# MUV_Sensors_pcb_all.net
KiCad netlist of a schematic drawn in EAGLE
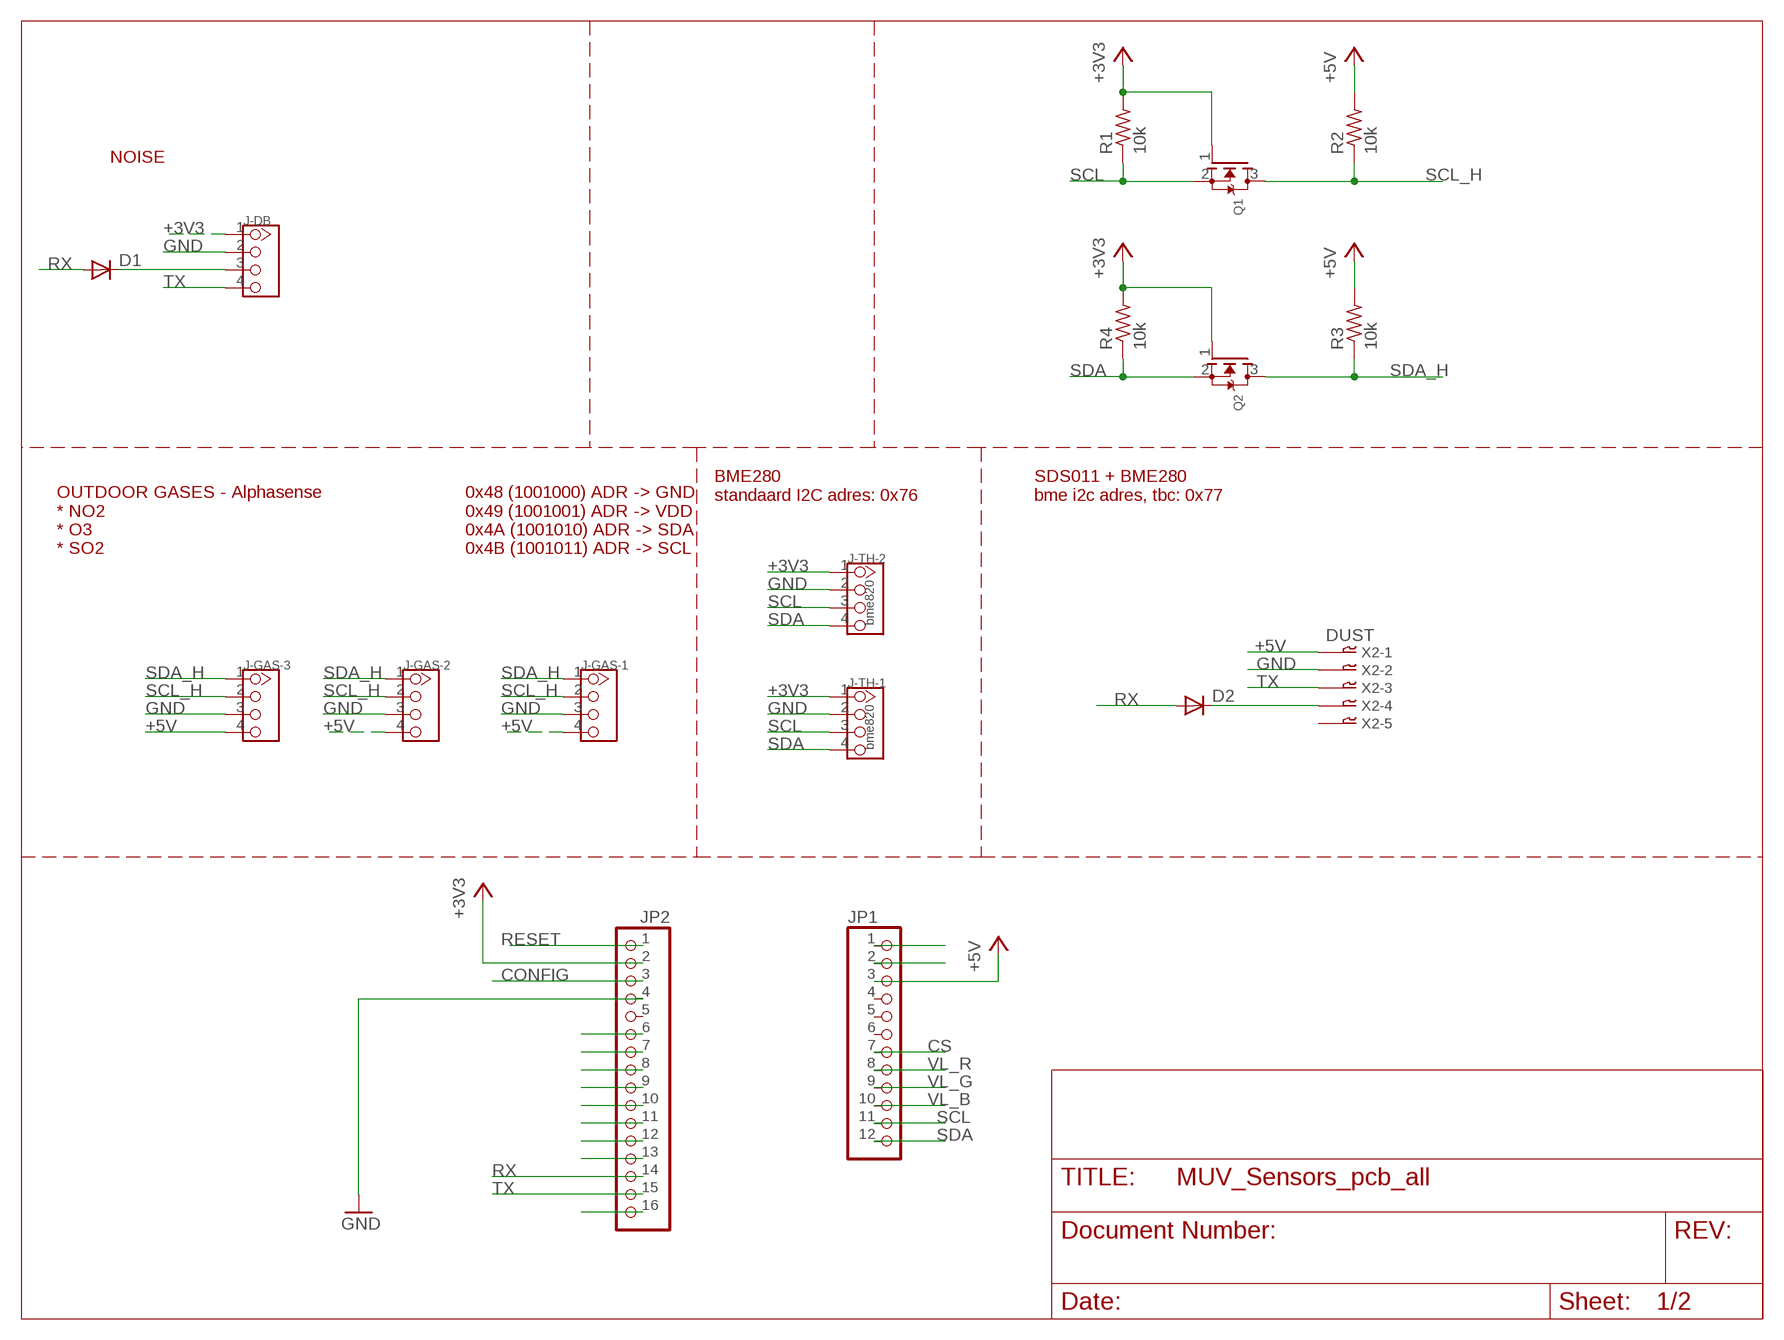
[diagram p0: schematic, sheet 1]

(export (version "E")
  (design (tool "Eeschema 10.0.6"))
  (components
    (comp (ref "D1")
      (value "DIODE-DO214AA")
      (footprint "eagle-import:DO214AA")
      (libsource (lib "eagle-import") (part "DIODE-DO214AA"))
    )
    (comp (ref "D2")
      (value "DIODE-DO214AA")
      (footprint "eagle-import:DO214AA")
      (libsource (lib "eagle-import") (part "DIODE-DO214AA"))
    )
    (comp (ref "J-DB")
      (value "TWIG-4P-2.0-2.0")
      (footprint "eagle-import:4P-2.0")
      (libsource (lib "eagle-import") (part "TWIG-4P-2.0-2.0"))
    )
    (comp (ref "J-GAS-1")
      (value "TWIG-4P-2.0-2.0")
      (footprint "eagle-import:4P-2.0")
      (libsource (lib "eagle-import") (part "TWIG-4P-2.0-2.0"))
    )
    (comp (ref "J-GAS-2")
      (value "TWIG-4P-2.0-2.0")
      (footprint "eagle-import:4P-2.0")
      (libsource (lib "eagle-import") (part "TWIG-4P-2.0-2.0"))
    )
    (comp (ref "J-GAS-3")
      (value "TWIG-4P-2.0-2.0")
      (footprint "eagle-import:4P-2.0")
      (libsource (lib "eagle-import") (part "TWIG-4P-2.0-2.0"))
    )
    (comp (ref "J-TH-1")
      (value "bme820")
      (footprint "eagle-import:4P-2.0")
      (libsource (lib "eagle-import") (part "TWIG-4P-2.0-2.0"))
    )
    (comp (ref "J-TH-2")
      (value "bme820")
      (footprint "eagle-import:4P-2.0")
      (libsource (lib "eagle-import") (part "TWIG-4P-2.0-2.0"))
    )
    (comp (ref "JP1")
      (value "HEADER-1X12OVAL")
      (footprint "eagle-import:1X12_OVAL")
      (libsource (lib "eagle-import") (part "HEADER-1X12OVAL"))
    )
    (comp (ref "JP2")
      (value "HEADER-1X16")
      (footprint "eagle-import:1X16_OVAL")
      (libsource (lib "eagle-import") (part "HEADER-1X16"))
    )
    (comp (ref "Q1")
      (value "MOSFET-NWIDE")
      (footprint "eagle-import:SOT23-WIDE")
      (libsource (lib "eagle-import") (part "MOSFET-NWIDE"))
    )
    (comp (ref "Q2")
      (value "MOSFET-NWIDE")
      (footprint "eagle-import:SOT23-WIDE")
      (libsource (lib "eagle-import") (part "MOSFET-NWIDE"))
    )
    (comp (ref "R1")
      (value "10k")
      (footprint "eagle-import:1206")
      (libsource (lib "eagle-import") (part "RESISTOR1206"))
    )
    (comp (ref "R2")
      (value "10k")
      (footprint "eagle-import:1206")
      (libsource (lib "eagle-import") (part "RESISTOR1206"))
    )
    (comp (ref "R3")
      (value "10k")
      (footprint "eagle-import:1206")
      (libsource (lib "eagle-import") (part "RESISTOR1206"))
    )
    (comp (ref "R4")
      (value "10k")
      (footprint "eagle-import:1206")
      (libsource (lib "eagle-import") (part "RESISTOR1206"))
    )
    (comp (ref "X2")
      (value "DUST")
      (footprint "eagle-import:B5B-XH")
      (libsource (lib "eagle-import") (part "05-JST-B5B-XH-A"))
    )
  )
  (nets
    (net (code "1") (name "+3V3") (class "Default")
      (node (ref "J-DB") (pin "1") (pinfunction "1_1") (pintype "bidirectional"))
      (node (ref "J-TH-1") (pin "1") (pinfunction "1_1") (pintype "bidirectional"))
      (node (ref "J-TH-2") (pin "1") (pinfunction "1_1") (pintype "bidirectional"))
      (node (ref "JP2") (pin "2") (pinfunction "2_2") (pintype "passive"))
      (node (ref "Q1") (pin "1") (pinfunction "G_1") (pintype "bidirectional"))
      (node (ref "Q2") (pin "1") (pinfunction "G_1") (pintype "bidirectional"))
      (node (ref "R1") (pin "2") (pinfunction "2_2") (pintype "passive"))
      (node (ref "R4") (pin "2") (pinfunction "2_2") (pintype "passive"))
    )
    (net (code "2") (name "+5V") (class "Default")
      (node (ref "J-GAS-1") (pin "4") (pinfunction "4_4") (pintype "bidirectional"))
      (node (ref "J-GAS-2") (pin "4") (pinfunction "4_4") (pintype "bidirectional"))
      (node (ref "J-GAS-3") (pin "4") (pinfunction "4_4") (pintype "bidirectional"))
      (node (ref "JP1") (pin "3") (pinfunction "3_3") (pintype "passive"))
      (node (ref "R2") (pin "2") (pinfunction "2_2") (pintype "passive"))
      (node (ref "R3") (pin "2") (pinfunction "2_2") (pintype "passive"))
      (node (ref "X2") (pin "P$1") (pinfunction "1_P$1") (pintype "passive"))
    )
    (net (code "3") (name "CONFIG") (class "Default")
      (node (ref "JP2") (pin "3") (pinfunction "3_3") (pintype "passive"))
    )
    (net (code "4") (name "CS") (class "Default")
      (node (ref "JP1") (pin "7") (pinfunction "7_7") (pintype "passive"))
    )
    (net (code "5") (name "GND") (class "Default")
      (node (ref "J-DB") (pin "2") (pinfunction "2_2") (pintype "bidirectional"))
      (node (ref "J-GAS-1") (pin "3") (pinfunction "3_3") (pintype "bidirectional"))
      (node (ref "J-GAS-2") (pin "3") (pinfunction "3_3") (pintype "bidirectional"))
      (node (ref "J-GAS-3") (pin "3") (pinfunction "3_3") (pintype "bidirectional"))
      (node (ref "J-TH-1") (pin "2") (pinfunction "2_2") (pintype "bidirectional"))
      (node (ref "J-TH-2") (pin "2") (pinfunction "2_2") (pintype "bidirectional"))
      (node (ref "JP2") (pin "4") (pinfunction "4_4") (pintype "passive"))
      (node (ref "X2") (pin "P$2") (pinfunction "1_P$2") (pintype "passive"))
    )
    (net (code "6") (name "Net-(D1-PadC)") (class "Default")
      (node (ref "D1") (pin "C") (pinfunction "C_C") (pintype "passive"))
      (node (ref "J-DB") (pin "3") (pinfunction "3_3") (pintype "bidirectional"))
    )
    (net (code "7") (name "Net-(X2D-1)") (class "Default")
      (node (ref "D2") (pin "C") (pinfunction "C_C") (pintype "passive"))
      (node (ref "X2") (pin "P$4") (pinfunction "1_P$4") (pintype "passive"))
    )
    (net (code "8") (name "RESET") (class "Default")
      (node (ref "JP2") (pin "1") (pinfunction "1_1") (pintype "passive"))
    )
    (net (code "9") (name "RX") (class "Default")
      (node (ref "D1") (pin "A") (pinfunction "A_A") (pintype "passive"))
      (node (ref "D2") (pin "A") (pinfunction "A_A") (pintype "passive"))
      (node (ref "JP2") (pin "14") (pinfunction "14_14") (pintype "passive"))
    )
    (net (code "10") (name "SCL") (class "Default")
      (node (ref "J-TH-1") (pin "3") (pinfunction "3_3") (pintype "bidirectional"))
      (node (ref "J-TH-2") (pin "3") (pinfunction "3_3") (pintype "bidirectional"))
      (node (ref "JP1") (pin "11") (pinfunction "11_11") (pintype "passive"))
      (node (ref "Q1") (pin "2") (pinfunction "S_2") (pintype "bidirectional"))
      (node (ref "R1") (pin "1") (pinfunction "1_1") (pintype "passive"))
    )
    (net (code "11") (name "SCL_H") (class "Default")
      (node (ref "J-GAS-1") (pin "2") (pinfunction "2_2") (pintype "bidirectional"))
      (node (ref "J-GAS-2") (pin "2") (pinfunction "2_2") (pintype "bidirectional"))
      (node (ref "J-GAS-3") (pin "2") (pinfunction "2_2") (pintype "bidirectional"))
      (node (ref "Q1") (pin "3") (pinfunction "D_3") (pintype "bidirectional"))
      (node (ref "R2") (pin "1") (pinfunction "1_1") (pintype "passive"))
    )
    (net (code "12") (name "SDA") (class "Default")
      (node (ref "J-TH-1") (pin "4") (pinfunction "4_4") (pintype "bidirectional"))
      (node (ref "J-TH-2") (pin "4") (pinfunction "4_4") (pintype "bidirectional"))
      (node (ref "JP1") (pin "12") (pinfunction "12_12") (pintype "passive"))
      (node (ref "Q2") (pin "2") (pinfunction "S_2") (pintype "bidirectional"))
      (node (ref "R4") (pin "1") (pinfunction "1_1") (pintype "passive"))
    )
    (net (code "13") (name "SDA_H") (class "Default")
      (node (ref "J-GAS-1") (pin "1") (pinfunction "1_1") (pintype "bidirectional"))
      (node (ref "J-GAS-2") (pin "1") (pinfunction "1_1") (pintype "bidirectional"))
      (node (ref "J-GAS-3") (pin "1") (pinfunction "1_1") (pintype "bidirectional"))
      (node (ref "Q2") (pin "3") (pinfunction "D_3") (pintype "bidirectional"))
      (node (ref "R3") (pin "1") (pinfunction "1_1") (pintype "passive"))
    )
    (net (code "14") (name "TX") (class "Default")
      (node (ref "J-DB") (pin "4") (pinfunction "4_4") (pintype "bidirectional"))
      (node (ref "JP2") (pin "15") (pinfunction "15_15") (pintype "passive"))
      (node (ref "X2") (pin "P$3") (pinfunction "1_P$3") (pintype "passive"))
    )
    (net (code "15") (name "VL_B") (class "Default")
      (node (ref "JP1") (pin "10") (pinfunction "10_10") (pintype "passive"))
    )
    (net (code "16") (name "VL_G") (class "Default")
      (node (ref "JP1") (pin "9") (pinfunction "9_9") (pintype "passive"))
    )
    (net (code "17") (name "VL_R") (class "Default")
      (node (ref "JP1") (pin "8") (pinfunction "8_8") (pintype "passive"))
    )
    (net (code "18") (name "unconnected-(JP1-Pad1)") (class "Default")
      (node (ref "JP1") (pin "1") (pinfunction "1_1") (pintype "passive"))
    )
    (net (code "19") (name "unconnected-(JP1-Pad2)") (class "Default")
      (node (ref "JP1") (pin "2") (pinfunction "2_2") (pintype "passive"))
    )
    (net (code "20") (name "unconnected-(JP1-Pad4)") (class "Default")
      (node (ref "JP1") (pin "4") (pinfunction "4_4") (pintype "passive"))
    )
    (net (code "21") (name "unconnected-(JP1-Pad5)") (class "Default")
      (node (ref "JP1") (pin "5") (pinfunction "5_5") (pintype "passive"))
    )
    (net (code "22") (name "unconnected-(JP1-Pad6)") (class "Default")
      (node (ref "JP1") (pin "6") (pinfunction "6_6") (pintype "passive"))
    )
    (net (code "23") (name "unconnected-(JP2-Pad5)") (class "Default")
      (node (ref "JP2") (pin "5") (pinfunction "5_5") (pintype "passive"))
    )
    (net (code "24") (name "unconnected-(JP2-Pad6)") (class "Default")
      (node (ref "JP2") (pin "6") (pinfunction "6_6") (pintype "passive"))
    )
    (net (code "25") (name "unconnected-(JP2-Pad7)") (class "Default")
      (node (ref "JP2") (pin "7") (pinfunction "7_7") (pintype "passive"))
    )
    (net (code "26") (name "unconnected-(JP2-Pad8)") (class "Default")
      (node (ref "JP2") (pin "8") (pinfunction "8_8") (pintype "passive"))
    )
    (net (code "27") (name "unconnected-(JP2-Pad9)") (class "Default")
      (node (ref "JP2") (pin "9") (pinfunction "9_9") (pintype "passive"))
    )
    (net (code "28") (name "unconnected-(JP2-Pad10)") (class "Default")
      (node (ref "JP2") (pin "10") (pinfunction "10_10") (pintype "passive"))
    )
    (net (code "29") (name "unconnected-(JP2-Pad11)") (class "Default")
      (node (ref "JP2") (pin "11") (pinfunction "11_11") (pintype "passive"))
    )
    (net (code "30") (name "unconnected-(JP2-Pad12)") (class "Default")
      (node (ref "JP2") (pin "12") (pinfunction "12_12") (pintype "passive"))
    )
    (net (code "31") (name "unconnected-(JP2-Pad13)") (class "Default")
      (node (ref "JP2") (pin "13") (pinfunction "13_13") (pintype "passive"))
    )
    (net (code "32") (name "unconnected-(JP2-Pad16)") (class "Default")
      (node (ref "JP2") (pin "16") (pinfunction "16_16") (pintype "passive"))
    )
    (net (code "33") (name "unconnected-(X2E-1-PadP$5)") (class "Default")
      (node (ref "X2") (pin "P$5") (pinfunction "1_P$5") (pintype "passive"))
    )
  )
)
